# ProjectFile.net
KiCad netlist of a schematic drawn in EasyEDA Pro
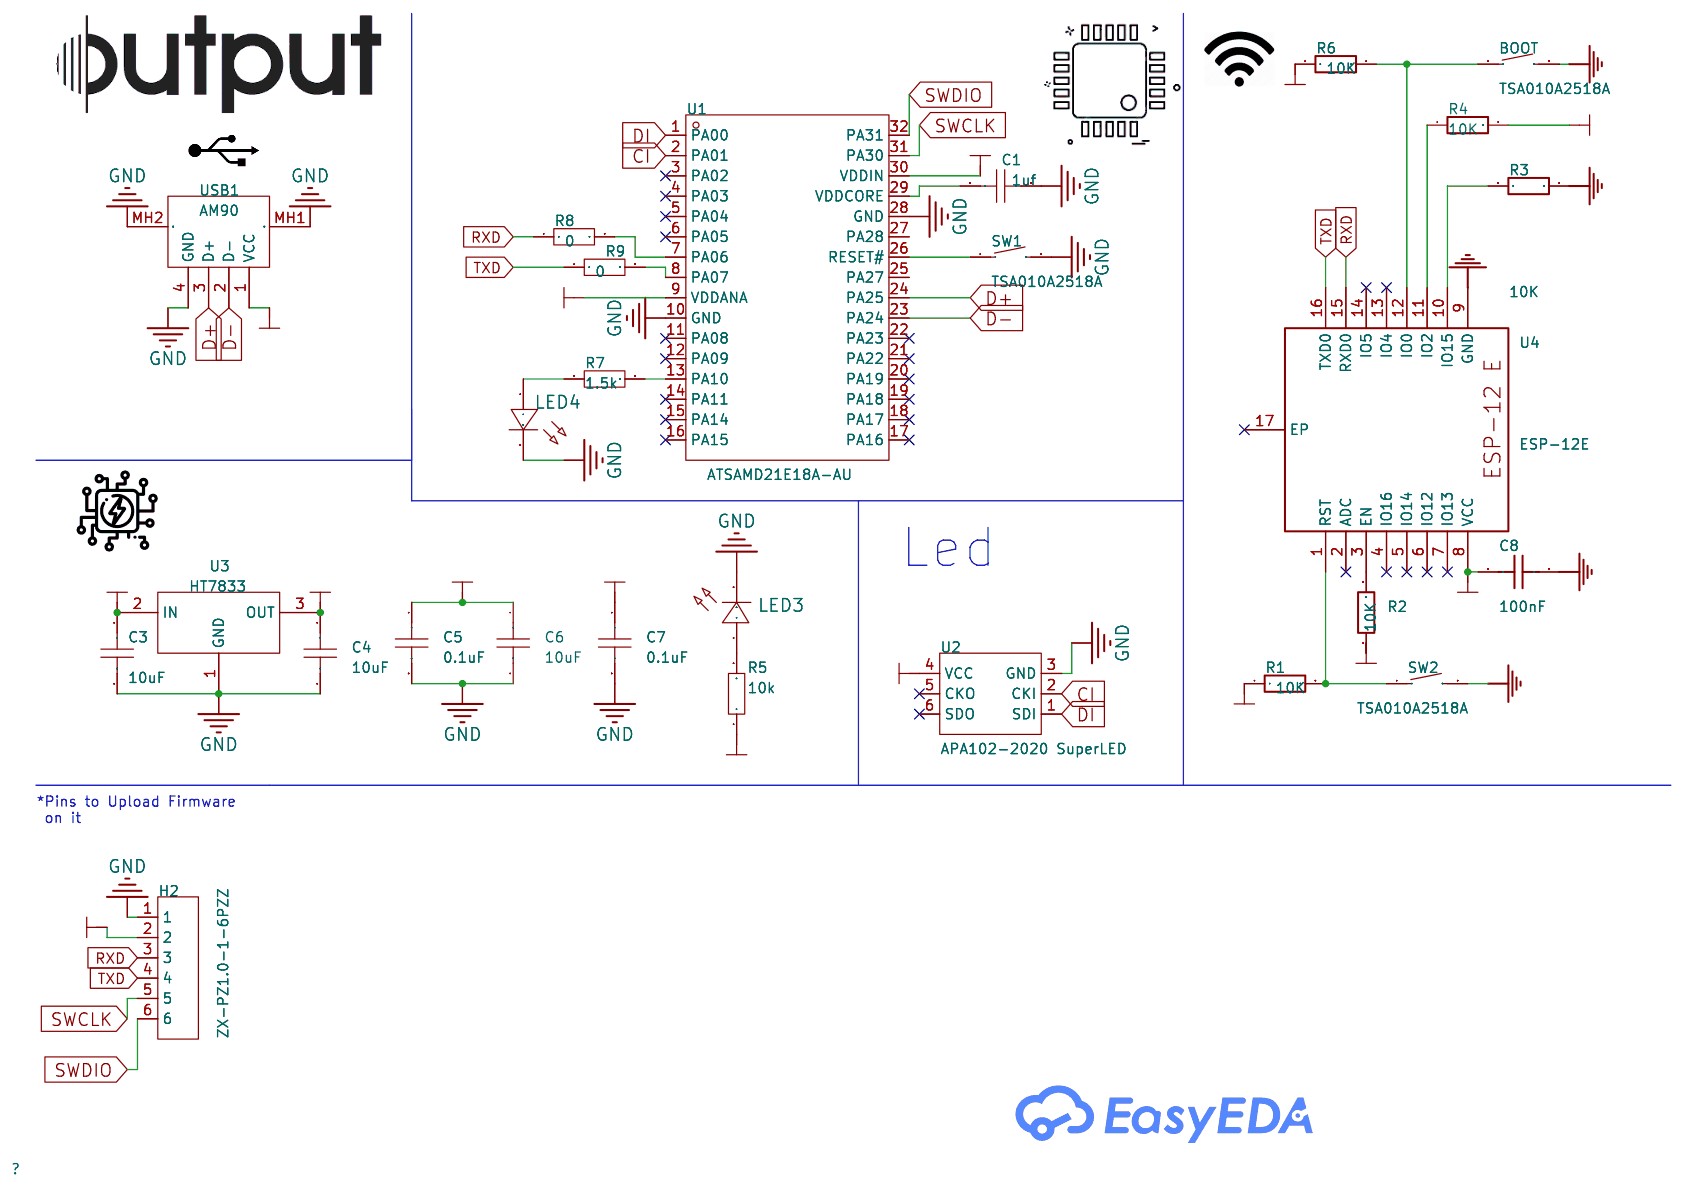
[diagram p0: schematic sheet]

(export (version "E")
  (design (tool "Eeschema 10.0.6"))
  (components
    (comp (ref "BOOT")
      (value "TSA010A2518A")
      (footprint "easyedapro:SW-SMD_L4.0-W3.0-LS5.0")
      (fields (field (name "Manufacturer") "BZCN(博众电气)"))
      (libsource (lib "easyedapro") (part "TSA010A2518A"))
    )
    (comp (ref "C1") (value "1uf") (footprint "easyedapro:C0603") (libsource (lib "easyedapro") (part "CAP")))
    (comp (ref "C3")
      (value "10uF")
      (footprint "easyedapro:C0603")
      (libsource (lib "easyedapro") (part "CAP"))
    )
    (comp (ref "C4")
      (value "10uF")
      (footprint "easyedapro:C0603")
      (libsource (lib "easyedapro") (part "CAP"))
    )
    (comp (ref "C5")
      (value "0.1uF")
      (footprint "easyedapro:C0603")
      (libsource (lib "easyedapro") (part "CAP"))
    )
    (comp (ref "C6")
      (value "10uF")
      (footprint "easyedapro:C0603")
      (libsource (lib "easyedapro") (part "CAP"))
    )
    (comp (ref "C7")
      (value "0.1uF")
      (footprint "easyedapro:C0603")
      (libsource (lib "easyedapro") (part "CAP"))
    )
    (comp (ref "C8")
      (value "100nF")
      (footprint "easyedapro:C1206")
      (fields
        (field (name "Manufacturer Part") "C1206C104K1RAC7800")
        (field (name "Manufacturer") "KEMET")
        (field (name "Contributor") "LCSC")
      )
      (libsource (lib "easyedapro") (part "100nF"))
    )
    (comp (ref "H2")
      (value "ZX-PZ1.0-1-6PZZ")
      (footprint "easyedapro:HDR-TH_6P-P1.00-V-F")
      (fields (field (name "Manufacturer") "Megastar(兆星)"))
      (libsource (lib "easyedapro") (part "ZX-PZ1.0-1-6PZZ"))
    )
    (comp (ref "LED3")
      (value "~")
      (footprint "easyedapro:LED0402-RD_YELLOW")
      (libsource (lib "easyedapro") (part "LED_R"))
    )
    (comp (ref "LED4")
      (value "~")
      (footprint "easyedapro:LED0402-RD_YELLOW")
      (libsource (lib "easyedapro") (part "LED_R"))
    )
    (comp (ref "R1")
      (value "10K")
      (footprint "easyedapro:R0805")
      (fields
        (field (name "Manufacturer Part") "PTFR0805B10K0N9")
        (field (name "Manufacturer") "ResistorToday")
        (field (name "Contributor") "LCSC")
      )
      (libsource (lib "easyedapro") (part "10K"))
    )
    (comp (ref "R2")
      (value "10K")
      (footprint "easyedapro:R0805")
      (fields
        (field (name "Manufacturer Part") "PTFR0805B10K0N9")
        (field (name "Manufacturer") "ResistorToday")
        (field (name "Contributor") "LCSC")
      )
      (libsource (lib "") (part "10K_2"))
    )
    (comp (ref "R3")
      (value "10K")
      (footprint "easyedapro:R0805")
      (fields
        (field (name "Manufacturer Part") "PTFR0805B10K0N9")
        (field (name "Manufacturer") "ResistorToday")
        (field (name "Contributor") "LCSC")
      )
      (libsource (lib "") (part "10K_1"))
    )
    (comp (ref "R4")
      (value "10K")
      (footprint "easyedapro:R0805")
      (fields
        (field (name "Manufacturer Part") "PTFR0805B10K0N9")
        (field (name "Manufacturer") "ResistorToday")
        (field (name "Contributor") "LCSC")
      )
      (libsource (lib "easyedapro") (part "10K"))
    )
    (comp (ref "R5") (value "10k") (footprint "easyedapro:R0603") (libsource (lib "easyedapro") (part "Res")))
    (comp (ref "R6")
      (value "10K")
      (footprint "easyedapro:R0805")
      (fields
        (field (name "Manufacturer Part") "PTFR0805B10K0N9")
        (field (name "Manufacturer") "ResistorToday")
        (field (name "Contributor") "LCSC")
      )
      (libsource (lib "") (part "10K_1"))
    )
    (comp (ref "R7")
      (value "1.5k")
      (footprint "easyedapro:R0603")
      (libsource (lib "easyedapro") (part "Res"))
    )
    (comp (ref "R8") (value "0") (footprint "easyedapro:R0603") (libsource (lib "easyedapro") (part "Res")))
    (comp (ref "R9") (value "0") (footprint "easyedapro:R0603") (libsource (lib "easyedapro") (part "Res")))
    (comp (ref "SW1")
      (value "TSA010A2518A")
      (footprint "easyedapro:SW-SMD_L4.0-W3.0-LS5.0")
      (fields (field (name "Manufacturer") "BZCN(博众电气)"))
      (libsource (lib "easyedapro") (part "TSA010A2518A"))
    )
    (comp (ref "SW2")
      (value "TSA010A2518A")
      (footprint "easyedapro:SW-SMD_L4.0-W3.0-LS5.0")
      (fields (field (name "Manufacturer") "BZCN(博众电气)"))
      (libsource (lib "easyedapro") (part "TSA010A2518A"))
    )
    (comp (ref "U1")
      (value "ATSAMD21E18A-AU")
      (footprint "easyedapro:TQFP-32_L7.0-W7.0-P0.80-LS9.0-BL")
      (fields (field (name "Manufacturer") "MICROCHIP(美国微芯)"))
      (libsource (lib "easyedapro") (part "ATSAMD21E18A-AU"))
    )
    (comp (ref "U2")
      (value "APA102-2020 SuperLED")
      (footprint "easyedapro:LED-SMD_6P-L2.0-W2.0-APA102-2020-SUPERLED")
      (fields (field (name "Manufacturer") "Led-Color(色彩光电)"))
      (libsource (lib "easyedapro") (part "APA102-2020 SUPERLED"))
    )
    (comp (ref "U3")
      (value "HT7833")
      (footprint "easyedapro:SOT-89_L4.5-W2.5-P1.50-LS4.2-BR")
      (description "+3V")
      (fields (field (name "Manufacturer") "HOLTEK(合泰/盛群)"))
      (libsource (lib "easyedapro") (part "HT7833"))
    )
    (comp (ref "U4")
      (value "ESP-12E")
      (footprint "easyedapro:WIRELM-SMD_ESP-12S")
      (fields
        (field (name "Manufacturer Part") "ESP-12S")
        (field (name "Manufacturer") "Ai-Thinker")
        (field (name "Contributor") "LCSC")
      )
      (libsource (lib "easyedapro") (part "ESP-12E"))
    )
    (comp (ref "USB1")
      (value "AM90")
      (footprint "easyedapro:USB-AM-TH_AM90")
      (fields (field (name "Manufacturer") "SHOU HAN(首韩)"))
      (libsource (lib "easyedapro") (part "AM90"))
    )
  )
  (nets
    (net (code "1") (name "+3V") (class "Default")
      (node (ref "C4") (pin "1") (pinfunction "1_1") (pintype "input"))
      (node (ref "C8") (pin "2") (pinfunction "2_2") (pintype "unspecified"))
      (node (ref "H2") (pin "2") (pinfunction "2_2") (pintype "unspecified"))
      (node (ref "R1") (pin "1") (pinfunction "1_1") (pintype "unspecified"))
      (node (ref "R2") (pin "1") (pinfunction "1_1") (pintype "unspecified"))
      (node (ref "R4") (pin "2") (pinfunction "2_2") (pintype "unspecified"))
      (node (ref "R5") (pin "1") (pinfunction "1_1") (pintype "input"))
      (node (ref "R6") (pin "2") (pinfunction "2_2") (pintype "unspecified"))
      (node (ref "U1") (pin "30") (pinfunction "VDDIN_30") (pintype "input"))
      (node (ref "U1") (pin "9") (pinfunction "VDDANA_9") (pintype "input"))
      (node (ref "U2") (pin "4") (pinfunction "VCC_4") (pintype "unspecified"))
      (node (ref "U3") (pin "3") (pinfunction "OUT_3") (pintype "unspecified"))
      (node (ref "U4") (pin "8") (pinfunction "VCC_8") (pintype "unspecified"))
    )
    (net (code "2") (name "CI") (class "Default")
      (node (ref "U1") (pin "2") (pinfunction "PA01_2") (pintype "input"))
      (node (ref "U2") (pin "2") (pinfunction "CKI_2") (pintype "unspecified"))
    )
    (net (code "3") (name "D+") (class "Default")
      (node (ref "U1") (pin "24") (pinfunction "PA25_24") (pintype "input"))
      (node (ref "USB1") (pin "3") (pinfunction "D+_3") (pintype "input"))
    )
    (net (code "4") (name "D-") (class "Default")
      (node (ref "U1") (pin "23") (pinfunction "PA24_23") (pintype "input"))
      (node (ref "USB1") (pin "2") (pinfunction "D-_2") (pintype "input"))
    )
    (net (code "5") (name "DI") (class "Default")
      (node (ref "U1") (pin "1") (pinfunction "PA00_1") (pintype "input"))
      (node (ref "U2") (pin "1") (pinfunction "SDI_1") (pintype "unspecified"))
    )
    (net (code "6") (name "GND") (class "Default")
      (node (ref "BOOT") (pin "2") (pinfunction "2_2") (pintype "unspecified"))
      (node (ref "C1") (pin "1") (pinfunction "1_1") (pintype "input"))
      (node (ref "C3") (pin "2") (pinfunction "2_2") (pintype "input"))
      (node (ref "C4") (pin "2") (pinfunction "2_2") (pintype "input"))
      (node (ref "C5") (pin "2") (pinfunction "2_2") (pintype "input"))
      (node (ref "C6") (pin "2") (pinfunction "2_2") (pintype "input"))
      (node (ref "C7") (pin "2") (pinfunction "2_2") (pintype "input"))
      (node (ref "C8") (pin "1") (pinfunction "1_1") (pintype "unspecified"))
      (node (ref "H2") (pin "1") (pinfunction "1_1") (pintype "unspecified"))
      (node (ref "LED3") (pin "2") (pinfunction "C_2") (pintype "input"))
      (node (ref "LED4") (pin "2") (pinfunction "C_2") (pintype "input"))
      (node (ref "R3") (pin "1") (pinfunction "1_1") (pintype "unspecified"))
      (node (ref "SW1") (pin "2") (pinfunction "2_2") (pintype "unspecified"))
      (node (ref "SW2") (pin "2") (pinfunction "2_2") (pintype "unspecified"))
      (node (ref "U1") (pin "10") (pinfunction "GND_10") (pintype "input"))
      (node (ref "U1") (pin "28") (pinfunction "GND_28") (pintype "input"))
      (node (ref "U2") (pin "3") (pinfunction "GND_3") (pintype "unspecified"))
      (node (ref "U3") (pin "1") (pinfunction "GND_1") (pintype "unspecified"))
      (node (ref "U4") (pin "9") (pinfunction "GND_9") (pintype "unspecified"))
      (node (ref "USB1") (pin "4") (pinfunction "GND_4") (pintype "input"))
      (node (ref "USB1") (pin "MH1") (pinfunction "MH1_MH1") (pintype "unspecified"))
      (node (ref "USB1") (pin "MH2") (pinfunction "MH2_MH2") (pintype "unspecified"))
    )
    (net (code "7") (name "Net-(LED3-A)") (class "Default")
      (node (ref "LED3") (pin "1") (pinfunction "A_1") (pintype "input"))
      (node (ref "R5") (pin "2") (pinfunction "2_2") (pintype "input"))
    )
    (net (code "8") (name "Net-(LED4-A)") (class "Default")
      (node (ref "LED4") (pin "1") (pinfunction "A_1") (pintype "input"))
      (node (ref "R7") (pin "1") (pinfunction "1_1") (pintype "input"))
    )
    (net (code "9") (name "Net-(U1-PA06)") (class "Default")
      (node (ref "R8") (pin "2") (pinfunction "2_2") (pintype "input"))
      (node (ref "U1") (pin "7") (pinfunction "PA06_7") (pintype "input"))
    )
    (net (code "10") (name "Net-(U1-PA07)") (class "Default")
      (node (ref "R9") (pin "2") (pinfunction "2_2") (pintype "input"))
      (node (ref "U1") (pin "8") (pinfunction "PA07_8") (pintype "input"))
    )
    (net (code "11") (name "Net-(U1-PA10)") (class "Default")
      (node (ref "R7") (pin "2") (pinfunction "2_2") (pintype "input"))
      (node (ref "U1") (pin "13") (pinfunction "PA10_13") (pintype "input"))
    )
    (net (code "12") (name "Net-(U1-RESET#)") (class "Default")
      (node (ref "SW1") (pin "1") (pinfunction "1_1") (pintype "unspecified"))
      (node (ref "U1") (pin "26") (pinfunction "RESET#_26") (pintype "input"))
    )
    (net (code "13") (name "Net-(U1-VDDCORE)") (class "Default")
      (node (ref "C1") (pin "2") (pinfunction "2_2") (pintype "input"))
      (node (ref "U1") (pin "29") (pinfunction "VDDCORE_29") (pintype "input"))
    )
    (net (code "14") (name "Net-(U4-EN)") (class "Default")
      (node (ref "R2") (pin "2") (pinfunction "2_2") (pintype "unspecified"))
      (node (ref "U4") (pin "3") (pinfunction "EN_3") (pintype "unspecified"))
    )
    (net (code "15") (name "Net-(U4-IO0)") (class "Default")
      (node (ref "BOOT") (pin "1") (pinfunction "1_1") (pintype "unspecified"))
      (node (ref "R6") (pin "1") (pinfunction "1_1") (pintype "unspecified"))
      (node (ref "U4") (pin "12") (pinfunction "IO0_12") (pintype "unspecified"))
    )
    (net (code "16") (name "Net-(U4-IO2)") (class "Default")
      (node (ref "R4") (pin "1") (pinfunction "1_1") (pintype "unspecified"))
      (node (ref "U4") (pin "11") (pinfunction "IO2_11") (pintype "unspecified"))
    )
    (net (code "17") (name "Net-(U4-IO15)") (class "Default")
      (node (ref "R3") (pin "2") (pinfunction "2_2") (pintype "unspecified"))
      (node (ref "U4") (pin "10") (pinfunction "IO15_10") (pintype "unspecified"))
    )
    (net (code "18") (name "Net-(U4-RST)") (class "Default")
      (node (ref "R1") (pin "2") (pinfunction "2_2") (pintype "unspecified"))
      (node (ref "SW2") (pin "1") (pinfunction "1_1") (pintype "unspecified"))
      (node (ref "U4") (pin "1") (pinfunction "RST_1") (pintype "unspecified"))
    )
    (net (code "19") (name "RXD") (class "Default")
      (node (ref "H2") (pin "3") (pinfunction "3_3") (pintype "unspecified"))
      (node (ref "R8") (pin "1") (pinfunction "1_1") (pintype "input"))
      (node (ref "U4") (pin "15") (pinfunction "RXD0_15") (pintype "unspecified"))
    )
    (net (code "20") (name "SWCLK") (class "Default")
      (node (ref "H2") (pin "5") (pinfunction "5_5") (pintype "unspecified"))
      (node (ref "U1") (pin "31") (pinfunction "PA30_31") (pintype "input"))
    )
    (net (code "21") (name "SWDIO") (class "Default")
      (node (ref "H2") (pin "6") (pinfunction "6_6") (pintype "unspecified"))
      (node (ref "U1") (pin "32") (pinfunction "PA31_32") (pintype "input"))
    )
    (net (code "22") (name "TXD") (class "Default")
      (node (ref "H2") (pin "4") (pinfunction "4_4") (pintype "unspecified"))
      (node (ref "R9") (pin "1") (pinfunction "1_1") (pintype "input"))
      (node (ref "U4") (pin "16") (pinfunction "TXD0_16") (pintype "unspecified"))
    )
    (net (code "23") (name "VBUS") (class "Default")
      (node (ref "C3") (pin "1") (pinfunction "1_1") (pintype "input"))
      (node (ref "C5") (pin "1") (pinfunction "1_1") (pintype "input"))
      (node (ref "C6") (pin "1") (pinfunction "1_1") (pintype "input"))
      (node (ref "C7") (pin "1") (pinfunction "1_1") (pintype "input"))
      (node (ref "U3") (pin "2") (pinfunction "IN_2") (pintype "unspecified"))
      (node (ref "USB1") (pin "1") (pinfunction "VCC_1") (pintype "input"))
    )
    (net (code "24") (name "unconnected-(U1-PA02-Pad3)") (class "Default")
      (node (ref "U1") (pin "3") (pinfunction "PA02_3") (pintype "input+no_connect"))
    )
    (net (code "25") (name "unconnected-(U1-PA03-Pad4)") (class "Default")
      (node (ref "U1") (pin "4") (pinfunction "PA03_4") (pintype "input+no_connect"))
    )
    (net (code "26") (name "unconnected-(U1-PA04-Pad5)") (class "Default")
      (node (ref "U1") (pin "5") (pinfunction "PA04_5") (pintype "input+no_connect"))
    )
    (net (code "27") (name "unconnected-(U1-PA05-Pad6)") (class "Default")
      (node (ref "U1") (pin "6") (pinfunction "PA05_6") (pintype "input+no_connect"))
    )
    (net (code "28") (name "unconnected-(U1-PA08-Pad11)") (class "Default")
      (node (ref "U1") (pin "11") (pinfunction "PA08_11") (pintype "input+no_connect"))
    )
    (net (code "29") (name "unconnected-(U1-PA09-Pad12)") (class "Default")
      (node (ref "U1") (pin "12") (pinfunction "PA09_12") (pintype "input+no_connect"))
    )
    (net (code "30") (name "unconnected-(U1-PA11-Pad14)") (class "Default")
      (node (ref "U1") (pin "14") (pinfunction "PA11_14") (pintype "input+no_connect"))
    )
    (net (code "31") (name "unconnected-(U1-PA14-Pad15)") (class "Default")
      (node (ref "U1") (pin "15") (pinfunction "PA14_15") (pintype "input+no_connect"))
    )
    (net (code "32") (name "unconnected-(U1-PA15-Pad16)") (class "Default")
      (node (ref "U1") (pin "16") (pinfunction "PA15_16") (pintype "input+no_connect"))
    )
    (net (code "33") (name "unconnected-(U1-PA16-Pad17)") (class "Default")
      (node (ref "U1") (pin "17") (pinfunction "PA16_17") (pintype "input+no_connect"))
    )
    (net (code "34") (name "unconnected-(U1-PA17-Pad18)") (class "Default")
      (node (ref "U1") (pin "18") (pinfunction "PA17_18") (pintype "input+no_connect"))
    )
    (net (code "35") (name "unconnected-(U1-PA18-Pad19)") (class "Default")
      (node (ref "U1") (pin "19") (pinfunction "PA18_19") (pintype "input+no_connect"))
    )
    (net (code "36") (name "unconnected-(U1-PA19-Pad20)") (class "Default")
      (node (ref "U1") (pin "20") (pinfunction "PA19_20") (pintype "input+no_connect"))
    )
    (net (code "37") (name "unconnected-(U1-PA22-Pad21)") (class "Default")
      (node (ref "U1") (pin "21") (pinfunction "PA22_21") (pintype "input+no_connect"))
    )
    (net (code "38") (name "unconnected-(U1-PA23-Pad22)") (class "Default")
      (node (ref "U1") (pin "22") (pinfunction "PA23_22") (pintype "input+no_connect"))
    )
    (net (code "39") (name "unconnected-(U1-PA27-Pad25)") (class "Default")
      (node (ref "U1") (pin "25") (pinfunction "PA27_25") (pintype "input"))
    )
    (net (code "40") (name "unconnected-(U1-PA28-Pad27)") (class "Default")
      (node (ref "U1") (pin "27") (pinfunction "PA28_27") (pintype "input"))
    )
    (net (code "41") (name "unconnected-(U2-CKO-Pad5)") (class "Default")
      (node (ref "U2") (pin "5") (pinfunction "CKO_5") (pintype "unspecified+no_connect"))
    )
    (net (code "42") (name "unconnected-(U2-SDO-Pad6)") (class "Default")
      (node (ref "U2") (pin "6") (pinfunction "SDO_6") (pintype "unspecified+no_connect"))
    )
    (net (code "43") (name "unconnected-(U4-ADC-Pad2)") (class "Default")
      (node (ref "U4") (pin "2") (pinfunction "ADC_2") (pintype "unspecified+no_connect"))
    )
    (net (code "44") (name "unconnected-(U4-EP-Pad17)") (class "Default")
      (node (ref "U4") (pin "17") (pinfunction "EP_17") (pintype "unspecified+no_connect"))
    )
    (net (code "45") (name "unconnected-(U4-IO4-Pad13)") (class "Default")
      (node (ref "U4") (pin "13") (pinfunction "IO4_13") (pintype "unspecified+no_connect"))
    )
    (net (code "46") (name "unconnected-(U4-IO5-Pad14)") (class "Default")
      (node (ref "U4") (pin "14") (pinfunction "IO5_14") (pintype "unspecified+no_connect"))
    )
    (net (code "47") (name "unconnected-(U4-IO12-Pad6)") (class "Default")
      (node (ref "U4") (pin "6") (pinfunction "IO12_6") (pintype "unspecified+no_connect"))
    )
    (net (code "48") (name "unconnected-(U4-IO13-Pad7)") (class "Default")
      (node (ref "U4") (pin "7") (pinfunction "IO13_7") (pintype "unspecified+no_connect"))
    )
    (net (code "49") (name "unconnected-(U4-IO14-Pad5)") (class "Default")
      (node (ref "U4") (pin "5") (pinfunction "IO14_5") (pintype "unspecified+no_connect"))
    )
    (net (code "50") (name "unconnected-(U4-IO16-Pad4)") (class "Default")
      (node (ref "U4") (pin "4") (pinfunction "IO16_4") (pintype "unspecified+no_connect"))
    )
  )
)
